# 1-Pic.net
KiCad netlist of a schematic drawn in Altium Designer
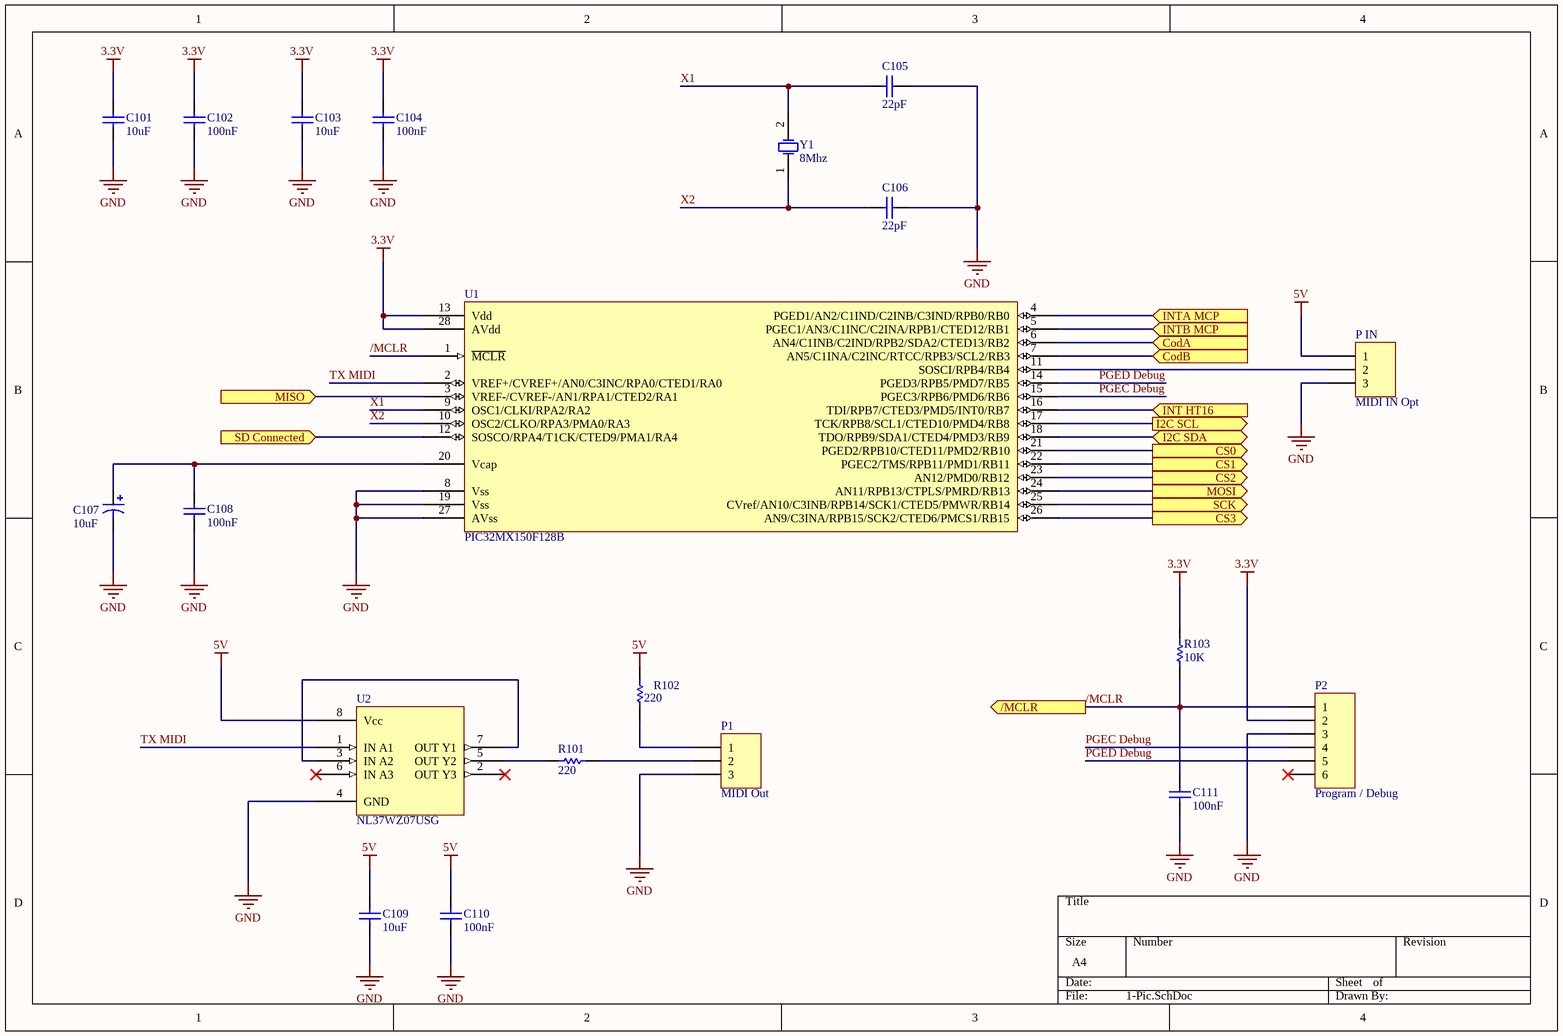
[diagram p0: 1-Pic.SchDoc]

(export (version "E")
  (design (tool "Eeschema 10.0.6"))
  (components
    (comp (ref "C101")
      (value "10uF")
      (footprint "capa 1206")
      (description "Capacitor")
      (libsource (lib "Miscellaneous Devices") (part "Cap"))
    )
    (comp (ref "C102")
      (value "100nF")
      (footprint "capa 1206")
      (description "Capacitor")
      (libsource (lib "Miscellaneous Devices") (part "Cap"))
    )
    (comp (ref "C103")
      (value "10uF")
      (footprint "capa 1206")
      (description "Capacitor")
      (libsource (lib "Miscellaneous Devices") (part "Cap"))
    )
    (comp (ref "C104")
      (value "100nF")
      (footprint "capa 1206")
      (description "Capacitor")
      (libsource (lib "Miscellaneous Devices") (part "Cap"))
    )
    (comp (ref "C105")
      (value "22pF")
      (footprint "capa 1206")
      (description "Capacitor")
      (libsource (lib "Miscellaneous Devices") (part "Cap"))
    )
    (comp (ref "C106")
      (value "22pF")
      (footprint "capa 1206")
      (description "Capacitor")
      (libsource (lib "Miscellaneous Devices") (part "Cap"))
    )
    (comp (ref "C107")
      (value "10uF")
      (footprint "CAPA 1206 POL")
      (description "Polarized Capacitor (Radial)")
      (libsource (lib "Miscellaneous Devices") (part "Cap Pol1"))
    )
    (comp (ref "C108")
      (value "100nF")
      (footprint "capa 1206")
      (description "Capacitor")
      (libsource (lib "Miscellaneous Devices") (part "Cap"))
    )
    (comp (ref "C109")
      (value "10uF")
      (footprint "capa 1206")
      (description "Capacitor")
      (libsource (lib "Miscellaneous Devices") (part "Cap"))
    )
    (comp (ref "C110")
      (value "100nF")
      (footprint "capa 1206")
      (description "Capacitor")
      (libsource (lib "Miscellaneous Devices") (part "Cap"))
    )
    (comp (ref "C111")
      (value "100nF")
      (footprint "capa 1206")
      (description "Capacitor")
      (libsource (lib "Miscellaneous Devices") (part "Cap"))
    )
    (comp (ref "P IN")
      (value "MIDI IN Opt")
      (footprint "MIDI")
      (description "Header, 3-Pin")
      (libsource (lib "Miscellaneous Connectors") (part "Header 3"))
    )
    (comp (ref "P1")
      (value "MIDI Out")
      (footprint "MIDI")
      (description "Header, 3-Pin")
      (libsource (lib "Miscellaneous Connectors") (part "Header 3"))
    )
    (comp (ref "P2")
      (value "Program / Debug")
      (footprint "HDR1X6")
      (description "Header, 6-Pin")
      (libsource (lib "Miscellaneous Connectors") (part "Header 6"))
    )
    (comp (ref "R101")
      (value "220")
      (footprint "RES 1206")
      (description "Resistor")
      (libsource (lib "Miscellaneous Devices") (part "Res1"))
    )
    (comp (ref "R102")
      (value "220")
      (footprint "RES 1206")
      (description "Resistor")
      (libsource (lib "Miscellaneous Devices") (part "Res1"))
    )
    (comp (ref "R103")
      (value "10K")
      (footprint "RES 1206")
      (description "Resistor")
      (libsource (lib "Miscellaneous Devices") (part "Res1"))
    )
    (comp (ref "U1")
      (value "PIC32MX150F128B")
      (footprint "PIC32MX150F128B-I/SO")
      (libsource (lib "0x2a002a") (part "PIC32MX150F128B"))
    )
    (comp (ref "U2")
      (value "NL37WZ07USG")
      (footprint "NL37WZ07USG")
      (libsource (lib "0x2a002a") (part "NL37WZ07USG"))
    )
    (comp (ref "Y1")
      (value "8Mhz")
      (footprint "HC49/4H SMX CRYSTAL")
      (description "Crystal Oscillator")
      (libsource (lib "Miscellaneous Devices") (part "XTAL"))
    )
  )
  (nets
    (net (code "1") (name "/CS0") (class "Default")
      (node (ref "U1") (pin "21") (pinfunction "PGED2/RPB10/CTED11/PMD2/RB10_21") (pintype "bidirectional"))
    )
    (net (code "2") (name "/CS1") (class "Default")
      (node (ref "U1") (pin "22") (pinfunction "PGEC2/TMS/RPB11/PMD1/RB11_22") (pintype "bidirectional"))
    )
    (net (code "3") (name "/CS2") (class "Default")
      (node (ref "U1") (pin "23") (pinfunction "AN12/PMD0/RB12_23") (pintype "bidirectional"))
    )
    (net (code "4") (name "/CS3") (class "Default")
      (node (ref "U1") (pin "26") (pinfunction "AN9/C3INA/RPB15/SCK2/CTED6/PMCS1/RB15_26") (pintype "bidirectional"))
    )
    (net (code "5") (name "/CodA") (class "Default")
      (node (ref "U1") (pin "6") (pinfunction "AN4/C1INB/C2IND/RPB2/SDA2/CTED13/RB2_6") (pintype "bidirectional"))
    )
    (net (code "6") (name "/CodB") (class "Default")
      (node (ref "U1") (pin "7") (pinfunction "AN5/C1INA/C2INC/RTCC/RPB3/SCL2/RB3_7") (pintype "bidirectional"))
    )
    (net (code "7") (name "/I2C SCL") (class "Default")
      (node (ref "U1") (pin "17") (pinfunction "TCK/RPB8/SCL1/CTED10/PMD4/RB8_17") (pintype "bidirectional"))
    )
    (net (code "8") (name "/I2C SDA") (class "Default")
      (node (ref "U1") (pin "18") (pinfunction "TDO/RPB9/SDA1/CTED4/PMD3/RB9_18") (pintype "bidirectional"))
    )
    (net (code "9") (name "/INT HT16") (class "Default")
      (node (ref "U1") (pin "16") (pinfunction "TDI/RPB7/CTED3/PMD5/INT0/RB7_16") (pintype "bidirectional"))
    )
    (net (code "10") (name "/INTA MCP") (class "Default")
      (node (ref "U1") (pin "4") (pinfunction "PGED1/AN2/C1IND/C2INB/C3IND/RPB0/RB0_4") (pintype "bidirectional"))
    )
    (net (code "11") (name "/INTB MCP") (class "Default")
      (node (ref "U1") (pin "5") (pinfunction "PGEC1/AN3/C1INC/C2INA/RPB1/CTED12/RB1_5") (pintype "bidirectional"))
    )
    (net (code "12") (name "/MISO") (class "Default")
      (node (ref "U1") (pin "3") (pinfunction "VREF-/CVREF-/AN1/RPA1/CTED2/RA1_3") (pintype "bidirectional"))
    )
    (net (code "13") (name "/MOSI") (class "Default")
      (node (ref "U1") (pin "24") (pinfunction "AN11/RPB13/CTPLS/PMRD/RB13_24") (pintype "bidirectional"))
    )
    (net (code "14") (name "/PGEC Debug") (class "Default")
      (node (ref "P2") (pin "4") (pinfunction "4_4") (pintype "passive"))
      (node (ref "U1") (pin "15") (pinfunction "PGEC3/RPB6/PMD6/RB6_15") (pintype "bidirectional"))
    )
    (net (code "15") (name "/PGED Debug") (class "Default")
      (node (ref "P2") (pin "5") (pinfunction "5_5") (pintype "passive"))
      (node (ref "U1") (pin "14") (pinfunction "PGED3/RPB5/PMD7/RB5_14") (pintype "bidirectional"))
    )
    (net (code "16") (name "/SCK") (class "Default")
      (node (ref "U1") (pin "25") (pinfunction "CVref/AN10/C3INB/RPB14/SCK1/CTED5/PMWR/RB14_25") (pintype "bidirectional"))
    )
    (net (code "17") (name "/SD Connected") (class "Default")
      (node (ref "U1") (pin "12") (pinfunction "SOSCO/RPA4/T1CK/CTED9/PMA1/RA4_12") (pintype "bidirectional"))
    )
    (net (code "18") (name "/TX MIDI") (class "Default")
      (node (ref "U1") (pin "2") (pinfunction "VREF+/CVREF+/AN0/C3INC/RPA0/CTED1/RA0_2") (pintype "bidirectional"))
      (node (ref "U2") (pin "1") (pinfunction "IN_A1_1") (pintype "input"))
    )
    (net (code "19") (name "/X1") (class "Default")
      (node (ref "C105") (pin "1") (pinfunction "1_1") (pintype "passive"))
      (node (ref "U1") (pin "9") (pinfunction "OSC1/CLKI/RPA2/RA2_9") (pintype "bidirectional"))
      (node (ref "Y1") (pin "2") (pinfunction "OSC2_2") (pintype "passive"))
    )
    (net (code "20") (name "/X2") (class "Default")
      (node (ref "C106") (pin "1") (pinfunction "1_1") (pintype "passive"))
      (node (ref "U1") (pin "10") (pinfunction "OSC2/CLKO/RPA3/PMA0/RA3_10") (pintype "bidirectional"))
      (node (ref "Y1") (pin "1") (pinfunction "OSC1_1") (pintype "passive"))
    )
    (net (code "21") (name "/{slash}MCLR") (class "Default")
      (node (ref "C111") (pin "2") (pinfunction "2_2") (pintype "passive"))
      (node (ref "P2") (pin "1") (pinfunction "1_1") (pintype "passive"))
      (node (ref "R103") (pin "1") (pinfunction "1_1") (pintype "passive"))
      (node (ref "U1") (pin "1") (pinfunction "~{MCLR}_1") (pintype "input"))
    )
    (net (code "22") (name "3.3V") (class "Default")
      (node (ref "C101") (pin "1") (pinfunction "1_1") (pintype "passive"))
      (node (ref "C102") (pin "1") (pinfunction "1_1") (pintype "passive"))
      (node (ref "C103") (pin "1") (pinfunction "1_1") (pintype "passive"))
      (node (ref "C104") (pin "1") (pinfunction "1_1") (pintype "passive"))
      (node (ref "P2") (pin "2") (pinfunction "2_2") (pintype "passive"))
      (node (ref "R103") (pin "2") (pinfunction "2_2") (pintype "passive"))
      (node (ref "U1") (pin "13") (pinfunction "Vdd_13") (pintype "power_in"))
      (node (ref "U1") (pin "28") (pinfunction "AVdd_28") (pintype "power_in"))
    )
    (net (code "23") (name "5V") (class "Default")
      (node (ref "C109") (pin "1") (pinfunction "1_1") (pintype "passive"))
      (node (ref "C110") (pin "1") (pinfunction "1_1") (pintype "passive"))
      (node (ref "P IN") (pin "1") (pinfunction "1_1") (pintype "passive"))
      (node (ref "R102") (pin "2") (pinfunction "2_2") (pintype "passive"))
      (node (ref "U2") (pin "8") (pinfunction "Vcc_8") (pintype "power_in"))
    )
    (net (code "24") (name "GND") (class "Default")
      (node (ref "C101") (pin "2") (pinfunction "2_2") (pintype "passive"))
      (node (ref "C102") (pin "2") (pinfunction "2_2") (pintype "passive"))
      (node (ref "C103") (pin "2") (pinfunction "2_2") (pintype "passive"))
      (node (ref "C104") (pin "2") (pinfunction "2_2") (pintype "passive"))
      (node (ref "C105") (pin "2") (pinfunction "2_2") (pintype "passive"))
      (node (ref "C106") (pin "2") (pinfunction "2_2") (pintype "passive"))
      (node (ref "C107") (pin "2") (pinfunction "2_2") (pintype "passive"))
      (node (ref "C108") (pin "2") (pinfunction "2_2") (pintype "passive"))
      (node (ref "C109") (pin "2") (pinfunction "2_2") (pintype "passive"))
      (node (ref "C110") (pin "2") (pinfunction "2_2") (pintype "passive"))
      (node (ref "C111") (pin "1") (pinfunction "1_1") (pintype "passive"))
      (node (ref "P IN") (pin "3") (pinfunction "3_3") (pintype "passive"))
      (node (ref "P1") (pin "3") (pinfunction "3_3") (pintype "passive"))
      (node (ref "P2") (pin "3") (pinfunction "3_3") (pintype "passive"))
      (node (ref "U1") (pin "19") (pinfunction "Vss_19") (pintype "power_in"))
      (node (ref "U1") (pin "27") (pinfunction "AVss_27") (pintype "power_in"))
      (node (ref "U1") (pin "8") (pinfunction "Vss_8") (pintype "power_in"))
      (node (ref "U2") (pin "4") (pinfunction "GND_4") (pintype "power_in"))
    )
    (net (code "25") (name "Net-(P1-Pad1)") (class "Default")
      (node (ref "P1") (pin "1") (pinfunction "1_1") (pintype "passive"))
      (node (ref "R102") (pin "1") (pinfunction "1_1") (pintype "passive"))
    )
    (net (code "26") (name "Net-(P1-Pad2)") (class "Default")
      (node (ref "P1") (pin "2") (pinfunction "2_2") (pintype "passive"))
      (node (ref "R101") (pin "1") (pinfunction "1_1") (pintype "passive"))
    )
    (net (code "27") (name "Net-(U1-SOSCI{slash}RPB4{slash}RB4)") (class "Default")
      (node (ref "P IN") (pin "2") (pinfunction "2_2") (pintype "passive"))
      (node (ref "U1") (pin "11") (pinfunction "SOSCI/RPB4/RB4_11") (pintype "bidirectional"))
    )
    (net (code "28") (name "Net-(U1-Vcap)") (class "Default")
      (node (ref "C107") (pin "1") (pinfunction "1_1") (pintype "passive"))
      (node (ref "C108") (pin "1") (pinfunction "1_1") (pintype "passive"))
      (node (ref "U1") (pin "20") (pinfunction "Vcap_20") (pintype "power_in"))
    )
    (net (code "29") (name "Net-(U2-IN_A2)") (class "Default")
      (node (ref "U2") (pin "3") (pinfunction "IN_A2_3") (pintype "input"))
      (node (ref "U2") (pin "7") (pinfunction "OUT_Y1_7") (pintype "output"))
    )
    (net (code "30") (name "Net-(U2-OUT_Y2)") (class "Default")
      (node (ref "R101") (pin "2") (pinfunction "2_2") (pintype "passive"))
      (node (ref "U2") (pin "5") (pinfunction "OUT_Y2_5") (pintype "output"))
    )
    (net (code "31") (name "unconnected-(P2-Pad6)") (class "Default")
      (node (ref "P2") (pin "6") (pinfunction "6_6") (pintype "passive+no_connect"))
    )
    (net (code "32") (name "unconnected-(U2-IN_A3-Pad6)") (class "Default")
      (node (ref "U2") (pin "6") (pinfunction "IN_A3_6") (pintype "input+no_connect"))
    )
    (net (code "33") (name "unconnected-(U2-OUT_Y3-Pad2)") (class "Default")
      (node (ref "U2") (pin "2") (pinfunction "OUT_Y3_2") (pintype "output+no_connect"))
    )
  )
)
